# HV_power.net
KiCad netlist of a schematic drawn in Altium Designer
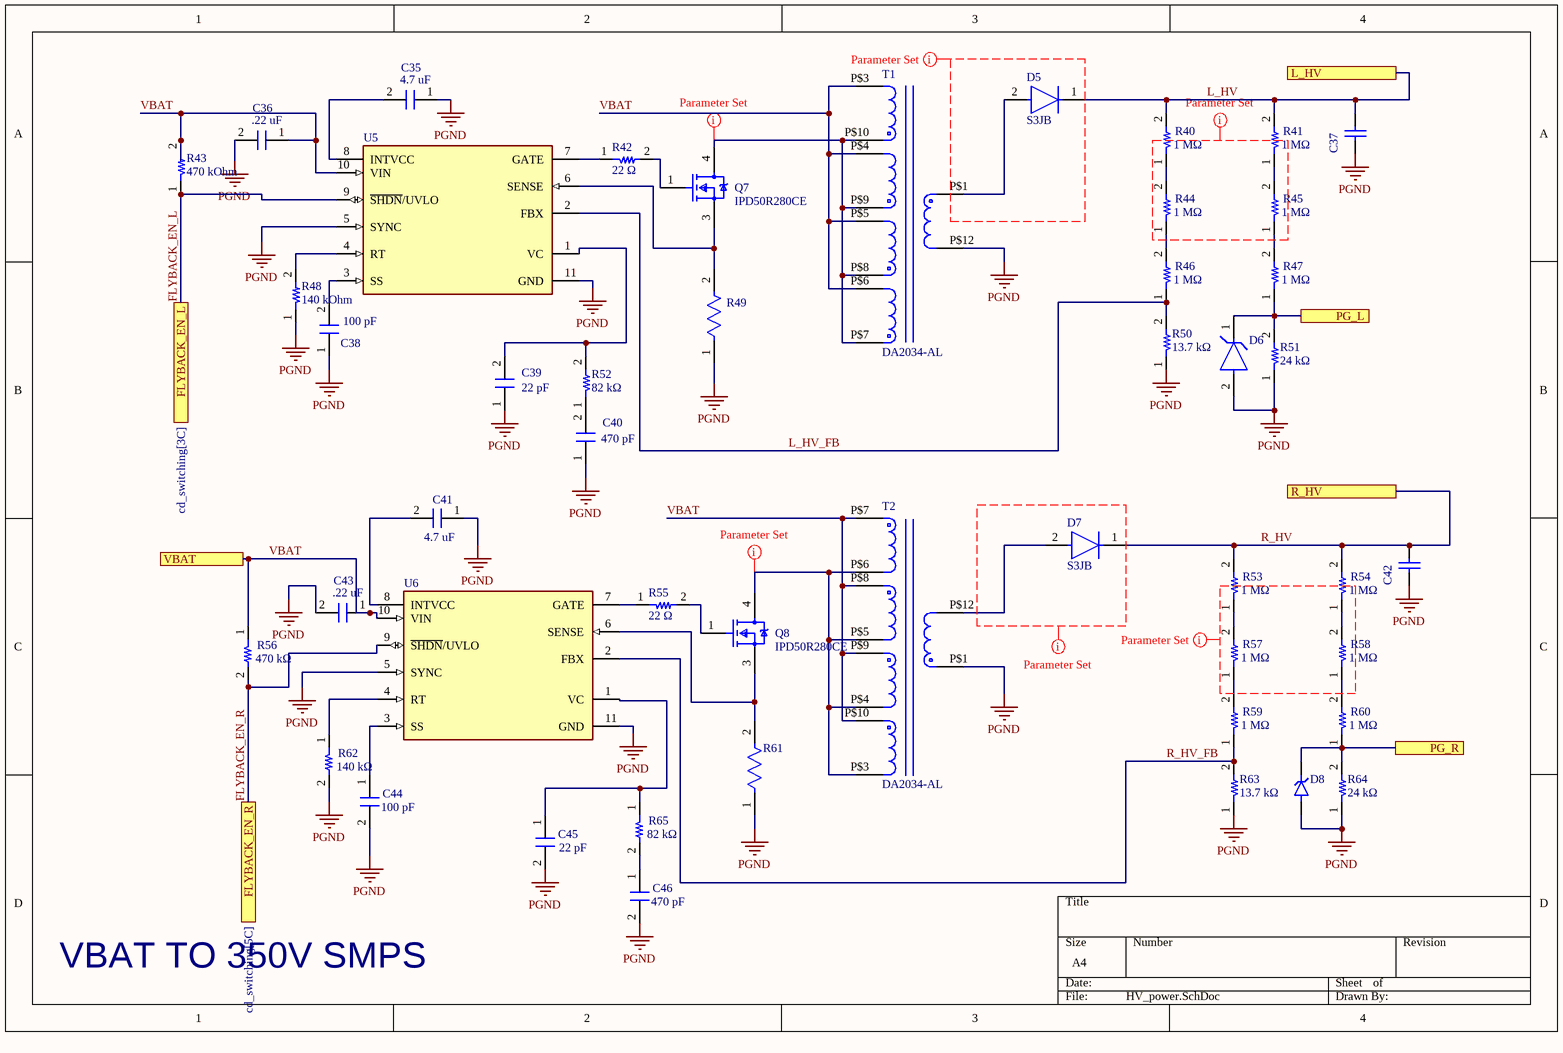
[diagram p0: HV_power.SchDoc]

(export (version "E")
  (design (tool "Eeschema 10.0.6"))
  (components
    (comp (ref "C35")
      (value "4.7 uF")
      (footprint "0603_FP")
      (fields (field (name "Comment") "GRM21BR61C475KA88L"))
      (libsource (lib "RC_sch") (part "Capacitor_0603"))
    )
    (comp (ref "C36")
      (value ".22 uF")
      (footprint "0603_FP")
      (fields (field (name "Comment") "GRM21BR61C475KA88L"))
      (libsource (lib "RC_sch") (part "Capacitor_0603"))
    )
    (comp (ref "C37")
      (value "890283323005CS")
      (footprint "WCAP-FTBP_L13W5.5H11")
      (description "Cap, 0.1Uf, 400V, Film, Radial Rohs Compliant: Yes")
      (libsource (lib "Altium Content Vault") (part "Capacitor_Non-Polarized"))
    )
    (comp (ref "C38")
      (value "100 pF")
      (footprint "0603_FP")
      (fields (field (name "Comment") "Capacitor_0603"))
      (libsource (lib "RC_sch") (part "Capacitor_0603"))
    )
    (comp (ref "C39")
      (value "22 pF")
      (footprint "0603_FP")
      (fields (field (name "Comment") "Capacitor_0603"))
      (libsource (lib "RC_sch") (part "Capacitor_0603"))
    )
    (comp (ref "C40")
      (value "470 pF")
      (footprint "0603_FP")
      (fields (field (name "Comment") "Capacitor_0603"))
      (libsource (lib "RC_sch") (part "Capacitor_0603"))
    )
    (comp (ref "C41")
      (value "4.7 uF")
      (footprint "0603_FP")
      (fields (field (name "Comment") "Capacitor_0603"))
      (libsource (lib "RC_sch") (part "Capacitor_0603"))
    )
    (comp (ref "C42")
      (value "890283323005CS")
      (footprint "WCAP-FTBP_L13W5.5H11")
      (description "Cap, 0.1Uf, 400V, Film, Radial Rohs Compliant: Yes")
      (libsource (lib "Altium Content Vault") (part "Capacitor_Non-Polarized"))
    )
    (comp (ref "C43")
      (value ".22 uF")
      (footprint "0603_FP")
      (fields (field (name "Comment") "GRM21BR61C475KA88L"))
      (libsource (lib "RC_sch") (part "Capacitor_0603"))
    )
    (comp (ref "C44")
      (value "100 pF")
      (footprint "0603_FP")
      (fields (field (name "Comment") "Capacitor_0603"))
      (libsource (lib "RC_sch") (part "Capacitor_0603"))
    )
    (comp (ref "C45")
      (value "22 pF")
      (footprint "0603_FP")
      (fields (field (name "Comment") "Capacitor_0603"))
      (libsource (lib "RC_sch") (part "Capacitor_0603"))
    )
    (comp (ref "C46")
      (value "470 pF")
      (footprint "0603_FP")
      (fields (field (name "Comment") "Capacitor_0603"))
      (libsource (lib "RC_sch") (part "Capacitor_0603"))
    )
    (comp (ref "D5")
      (value "S3JB")
      (footprint "FP-403AF-MFG")
      (description "S3JB Rectifier Diode, 1 Phase, 1 Element, 3A, 600V V(RRM), Silicon, DO-214AA")
      (libsource (lib "Altium Content Vault") (part "e8bb5000357cae87636711d27716c66"))
    )
    (comp (ref "D6")
      (value "CZRQR3V3B-HF")
      (footprint "FP-0402-SOD-923F-MFG")
      (description "DIODE ZENER 3.3V 125MW 0402")
      (fields (field (name "TOLERANCE") "5%"))
      (libsource (lib "Altium Content Vault") (part "f813f71cba58e380607f5dd3caf9714"))
    )
    (comp (ref "D7")
      (value "S3JB")
      (footprint "FP-403AF-MFG")
      (description "S3JB Rectifier Diode, 1 Phase, 1 Element, 3A, 600V V(RRM), Silicon, DO-214AA")
      (libsource (lib "Altium Content Vault") (part "e8bb5000357cae87636711d27716c66"))
    )
    (comp (ref "D8")
      (value "BZT52B15SH_RRG")
      (footprint "DIO_BZT52B15SH_RRG")
      (description "SOD-323, 200mW, 2%, 15V, Zener Diode")
      (fields (field (name "MF") "Taiwan Semiconductor Corporation") (field (name "MP") "BZT52B15SH RRG"))
      (libsource (lib "BZT52B15SH_RRG") (part "BZT52B15SH_RRG"))
    )
    (comp (ref "Q7")
      (value "IPD50R280CE")
      (footprint "FP-PG-TO252-3-MFG")
      (description "MOSFET N-CH 30V 161A DPAK")
      (fields
        (field (name "OCTOPART") "https://octopart.com/irlr7843trpbf-infineon-65875062")
        (field (name "MANUFACTURER PART NUMBER") "IRLR7843TRPBF")
      )
      (libsource (lib "Altium Content Vault") (part "2f21c11e83d30f418bb422e5a3b3d11"))
    )
    (comp (ref "Q8")
      (value "IPD50R280CE")
      (footprint "FP-PG-TO252-3-MFG")
      (description "MOSFET N-CH 30V 161A DPAK")
      (fields
        (field (name "OCTOPART") "https://octopart.com/irlr7843trpbf-infineon-65875062")
        (field (name "MANUFACTURER PART NUMBER") "IRLR7843TRPBF")
      )
      (libsource (lib "Altium Content Vault") (part "2f21c11e83d30f418bb422e5a3b3d11"))
    )
    (comp (ref "R40")
      (value "1 MΩ")
      (footprint "0805_FP")
      (fields (field (name "Comment") "R_0805"))
      (libsource (lib "0805_R") (part "R_0805"))
    )
    (comp (ref "R41")
      (value "1 MΩ")
      (footprint "0805_FP")
      (fields (field (name "Comment") "R_0805"))
      (libsource (lib "0805_R") (part "R_0805"))
    )
    (comp (ref "R42")
      (value "22 Ω")
      (footprint "0603_FP")
      (fields (field (name "Comment") "Resistor_0603"))
      (libsource (lib "RC_sch") (part "Resistor_0603"))
    )
    (comp (ref "R43")
      (value "470 kOhm")
      (footprint "0603_FP")
      (fields (field (name "Comment") "Resistor_0603"))
      (libsource (lib "RC_sch") (part "Resistor_0603"))
    )
    (comp (ref "R44")
      (value "1 MΩ")
      (footprint "0805_FP")
      (fields (field (name "Comment") "R_0805"))
      (libsource (lib "0805_R") (part "R_0805"))
    )
    (comp (ref "R45")
      (value "1 MΩ")
      (footprint "0805_FP")
      (fields (field (name "Comment") "R_0805"))
      (libsource (lib "0805_R") (part "R_0805"))
    )
    (comp (ref "R46")
      (value "1 MΩ")
      (footprint "0805_FP")
      (fields (field (name "Comment") "R_0805"))
      (libsource (lib "0805_R") (part "R_0805"))
    )
    (comp (ref "R47")
      (value "1 MΩ")
      (footprint "0805_FP")
      (fields (field (name "Comment") "R_0805"))
      (libsource (lib "0805_R") (part "R_0805"))
    )
    (comp (ref "R48")
      (value "140 kOhm")
      (footprint "0603_FP")
      (fields (field (name "Comment") "Resistor_0603"))
      (libsource (lib "RC_sch") (part "Resistor_0603"))
    )
    (comp (ref "R49")
      (value "CSRN2010FK20L0")
      (footprint "FP-CSRN2010-IPC_B")
      (description "Res Thick Film 2010 20mΩ 1% 1W ±250ppm/°C Molded SMD Plastic T/R")
      (fields (field (name "TOLERANCE") "1%"))
      (libsource (lib "Altium Content Vault") (part "1029c3af85768c4190bb7ad29bc67b5"))
    )
    (comp (ref "R50")
      (value "13.7 kΩ")
      (footprint "0805_FP")
      (fields (field (name "Comment") "R_0805"))
      (libsource (lib "0805_R") (part "R_0805"))
    )
    (comp (ref "R51")
      (value "24 kΩ")
      (footprint "0805_FP")
      (fields (field (name "Comment") "R_0805"))
      (libsource (lib "0805_R") (part "R_0805"))
    )
    (comp (ref "R52")
      (value "82 kΩ")
      (footprint "0603_FP")
      (fields (field (name "Comment") "Resistor_0603"))
      (libsource (lib "RC_sch") (part "Resistor_0603"))
    )
    (comp (ref "R53")
      (value "1 MΩ")
      (footprint "0805_FP")
      (fields (field (name "Comment") "R_0805"))
      (libsource (lib "0805_R") (part "R_0805"))
    )
    (comp (ref "R54")
      (value "1 MΩ")
      (footprint "0805_FP")
      (fields (field (name "Comment") "R_0805"))
      (libsource (lib "0805_R") (part "R_0805"))
    )
    (comp (ref "R55")
      (value "22 Ω")
      (footprint "0603_FP")
      (fields (field (name "Comment") "Resistor_0603"))
      (libsource (lib "RC_sch") (part "Resistor_0603"))
    )
    (comp (ref "R56")
      (value "470 kΩ")
      (footprint "0603_FP")
      (fields (field (name "Comment") "Resistor_0603"))
      (libsource (lib "RC_sch") (part "Resistor_0603"))
    )
    (comp (ref "R57")
      (value "1 MΩ")
      (footprint "0805_FP")
      (fields (field (name "Comment") "R_0805"))
      (libsource (lib "0805_R") (part "R_0805"))
    )
    (comp (ref "R58")
      (value "1 MΩ")
      (footprint "0805_FP")
      (fields (field (name "Comment") "R_0805"))
      (libsource (lib "0805_R") (part "R_0805"))
    )
    (comp (ref "R59")
      (value "1 MΩ")
      (footprint "0805_FP")
      (fields (field (name "Comment") "R_0805"))
      (libsource (lib "0805_R") (part "R_0805"))
    )
    (comp (ref "R60")
      (value "1 MΩ")
      (footprint "0805_FP")
      (fields (field (name "Comment") "R_0805"))
      (libsource (lib "0805_R") (part "R_0805"))
    )
    (comp (ref "R61")
      (value "CSRN2010FK20L0")
      (footprint "FP-CSRN2010-IPC_B")
      (description "Res Thick Film 2010 20mΩ 1% 1W ±250ppm/°C Molded SMD Plastic T/R")
      (fields (field (name "TOLERANCE") "1%"))
      (libsource (lib "Altium Content Vault") (part "1029c3af85768c4190bb7ad29bc67b5"))
    )
    (comp (ref "R62")
      (value "140 kΩ")
      (footprint "0603_FP")
      (fields (field (name "Comment") "Resistor_0603"))
      (libsource (lib "RC_sch") (part "Resistor_0603"))
    )
    (comp (ref "R63")
      (value "13.7 kΩ")
      (footprint "0805_FP")
      (fields (field (name "Comment") "R_0805"))
      (libsource (lib "0805_R") (part "R_0805"))
    )
    (comp (ref "R64")
      (value "24 kΩ")
      (footprint "0805_FP")
      (fields (field (name "Comment") "R_0805"))
      (libsource (lib "0805_R") (part "R_0805"))
    )
    (comp (ref "R65")
      (value "82 kΩ")
      (footprint "0603_FP")
      (fields (field (name "Comment") "Resistor_0603"))
      (libsource (lib "RC_sch") (part "Resistor_0603"))
    )
    (comp (ref "T1")
      (value "DA2034-AL")
      (footprint "DA2034-AL")
      (libsource (lib "DA2034-AL") (part "DA2034-AL"))
    )
    (comp (ref "T2")
      (value "DA2034-AL")
      (footprint "DA2034-AL")
      (libsource (lib "DA2034-AL") (part "DA2034-AL"))
    )
    (comp (ref "U5")
      (value "LT3758EDD#PBF")
      (footprint "FP-DD-10-05-08-1699-IPC_B")
      (description "IC REG CTRLR MULT TOPOLOGY 10DFN")
      (libsource (lib "Altium Content Vault") (part "079e3863d39c5e5796f69dc810f510e"))
    )
    (comp (ref "U6")
      (value "LT3758EDD#PBF")
      (footprint "FP-DD-10-05-08-1699-IPC_B")
      (description "IC REG CTRLR MULT TOPOLOGY 10DFN")
      (libsource (lib "Altium Content Vault") (part "079e3863d39c5e5796f69dc810f510e"))
    )
  )
  (nets
    (net (code "1") (name "/FLYBACK_EN_L") (class "Default")
      (node (ref "R43") (pin "1") (pinfunction "1_1") (pintype "passive"))
      (node (ref "U5") (pin "9") (pinfunction "~{SHDN}/UVLO_9") (pintype "bidirectional"))
    )
    (net (code "2") (name "/FLYBACK_EN_R") (class "Default")
      (node (ref "R56") (pin "2") (pinfunction "2_2") (pintype "passive"))
      (node (ref "U6") (pin "9") (pinfunction "~{SHDN}/UVLO_9") (pintype "bidirectional"))
    )
    (net (code "3") (name "/L_HV") (class "Default")
      (node (ref "C37") (pin "2") (pinfunction "2_2") (pintype "passive"))
      (node (ref "D5") (pin "1") (pinfunction "C_1") (pintype "passive"))
      (node (ref "R40") (pin "2") (pinfunction "2_2") (pintype "passive"))
      (node (ref "R41") (pin "2") (pinfunction "2_2") (pintype "passive"))
    )
    (net (code "4") (name "/L_HV_FB") (class "Default")
      (node (ref "R46") (pin "1") (pinfunction "1_1") (pintype "passive"))
      (node (ref "R50") (pin "2") (pinfunction "2_2") (pintype "passive"))
      (node (ref "U5") (pin "2") (pinfunction "FBX_2") (pintype "passive"))
    )
    (net (code "5") (name "/PG_L") (class "Default")
      (node (ref "D6") (pin "1") (pinfunction "C_1") (pintype "passive"))
      (node (ref "R47") (pin "1") (pinfunction "1_1") (pintype "passive"))
      (node (ref "R51") (pin "2") (pinfunction "2_2") (pintype "passive"))
    )
    (net (code "6") (name "/PG_R") (class "Default")
      (node (ref "D8") (pin "1") (pinfunction "K_1") (pintype "passive"))
      (node (ref "R60") (pin "1") (pinfunction "1_1") (pintype "passive"))
      (node (ref "R64") (pin "2") (pinfunction "2_2") (pintype "passive"))
    )
    (net (code "7") (name "/R_HV") (class "Default")
      (node (ref "C42") (pin "2") (pinfunction "2_2") (pintype "passive"))
      (node (ref "D7") (pin "1") (pinfunction "C_1") (pintype "passive"))
      (node (ref "R53") (pin "2") (pinfunction "2_2") (pintype "passive"))
      (node (ref "R54") (pin "2") (pinfunction "2_2") (pintype "passive"))
    )
    (net (code "8") (name "/R_HV_FB") (class "Default")
      (node (ref "R59") (pin "1") (pinfunction "1_1") (pintype "passive"))
      (node (ref "R63") (pin "2") (pinfunction "2_2") (pintype "passive"))
      (node (ref "U6") (pin "2") (pinfunction "FBX_2") (pintype "passive"))
    )
    (net (code "9") (name "/VBAT") (class "Default")
      (node (ref "C36") (pin "1") (pinfunction "1_1") (pintype "passive"))
      (node (ref "C43") (pin "1") (pinfunction "1_1") (pintype "passive"))
      (node (ref "R43") (pin "2") (pinfunction "2_2") (pintype "passive"))
      (node (ref "R56") (pin "1") (pinfunction "1_1") (pintype "passive"))
      (node (ref "T1") (pin "P$3") (pinfunction "3_P$3") (pintype "passive"))
      (node (ref "T1") (pin "P$4") (pinfunction "4_P$4") (pintype "passive"))
      (node (ref "T1") (pin "P$5") (pinfunction "5_P$5") (pintype "passive"))
      (node (ref "T1") (pin "P$6") (pinfunction "6_P$6") (pintype "passive"))
      (node (ref "T2") (pin "P$10") (pinfunction "10_P$10") (pintype "passive"))
      (node (ref "T2") (pin "P$7") (pinfunction "7_P$7") (pintype "passive"))
      (node (ref "T2") (pin "P$8") (pinfunction "8_P$8") (pintype "passive"))
      (node (ref "T2") (pin "P$9") (pinfunction "9_P$9") (pintype "passive"))
      (node (ref "U5") (pin "10") (pinfunction "VIN_10") (pintype "input"))
      (node (ref "U6") (pin "10") (pinfunction "VIN_10") (pintype "input"))
    )
    (net (code "10") (name "Net-(C40-Pad2)") (class "Default")
      (node (ref "C40") (pin "2") (pinfunction "2_2") (pintype "passive"))
      (node (ref "R52") (pin "1") (pinfunction "1_1") (pintype "passive"))
    )
    (net (code "11") (name "Net-(C46-Pad1)") (class "Default")
      (node (ref "C46") (pin "1") (pinfunction "1_1") (pintype "passive"))
      (node (ref "R65") (pin "2") (pinfunction "2_2") (pintype "passive"))
    )
    (net (code "12") (name "Net-(D5-A)") (class "Default")
      (node (ref "D5") (pin "2") (pinfunction "A_2") (pintype "passive"))
      (node (ref "T1") (pin "P$1") (pinfunction "1_P$1") (pintype "passive"))
    )
    (net (code "13") (name "Net-(D7-A)") (class "Default")
      (node (ref "D7") (pin "2") (pinfunction "A_2") (pintype "passive"))
      (node (ref "T2") (pin "P$12") (pinfunction "12_P$12") (pintype "passive"))
    )
    (net (code "14") (name "Net-(Q7-DRAIN)") (class "Default")
      (node (ref "Q7") (pin "4") (pinfunction "DRAIN_4") (pintype "passive"))
      (node (ref "T1") (pin "P$10") (pinfunction "10_P$10") (pintype "passive"))
      (node (ref "T1") (pin "P$7") (pinfunction "7_P$7") (pintype "passive"))
      (node (ref "T1") (pin "P$8") (pinfunction "8_P$8") (pintype "passive"))
      (node (ref "T1") (pin "P$9") (pinfunction "9_P$9") (pintype "passive"))
    )
    (net (code "15") (name "Net-(Q7-GATE)") (class "Default")
      (node (ref "Q7") (pin "1") (pinfunction "GATE_1") (pintype "passive"))
      (node (ref "R42") (pin "2") (pinfunction "2_2") (pintype "passive"))
    )
    (net (code "16") (name "Net-(Q7-SOURCE)") (class "Default")
      (node (ref "Q7") (pin "3") (pinfunction "SOURCE_3") (pintype "passive"))
      (node (ref "R49") (pin "2") (pinfunction "2_2") (pintype "passive"))
      (node (ref "U5") (pin "6") (pinfunction "SENSE_6") (pintype "input"))
    )
    (net (code "17") (name "Net-(Q8-DRAIN)") (class "Default")
      (node (ref "Q8") (pin "4") (pinfunction "DRAIN_4") (pintype "passive"))
      (node (ref "T2") (pin "P$3") (pinfunction "3_P$3") (pintype "passive"))
      (node (ref "T2") (pin "P$4") (pinfunction "4_P$4") (pintype "passive"))
      (node (ref "T2") (pin "P$5") (pinfunction "5_P$5") (pintype "passive"))
      (node (ref "T2") (pin "P$6") (pinfunction "6_P$6") (pintype "passive"))
    )
    (net (code "18") (name "Net-(Q8-GATE)") (class "Default")
      (node (ref "Q8") (pin "1") (pinfunction "GATE_1") (pintype "passive"))
      (node (ref "R55") (pin "2") (pinfunction "2_2") (pintype "passive"))
    )
    (net (code "19") (name "Net-(Q8-SOURCE)") (class "Default")
      (node (ref "Q8") (pin "3") (pinfunction "SOURCE_3") (pintype "passive"))
      (node (ref "R61") (pin "2") (pinfunction "2_2") (pintype "passive"))
      (node (ref "U6") (pin "6") (pinfunction "SENSE_6") (pintype "input"))
    )
    (net (code "20") (name "Net-(R40-Pad1)") (class "Default")
      (node (ref "R40") (pin "1") (pinfunction "1_1") (pintype "passive"))
      (node (ref "R44") (pin "2") (pinfunction "2_2") (pintype "passive"))
    )
    (net (code "21") (name "Net-(R41-Pad1)") (class "Default")
      (node (ref "R41") (pin "1") (pinfunction "1_1") (pintype "passive"))
      (node (ref "R45") (pin "2") (pinfunction "2_2") (pintype "passive"))
    )
    (net (code "22") (name "Net-(R44-Pad1)") (class "Default")
      (node (ref "R44") (pin "1") (pinfunction "1_1") (pintype "passive"))
      (node (ref "R46") (pin "2") (pinfunction "2_2") (pintype "passive"))
    )
    (net (code "23") (name "Net-(R45-Pad1)") (class "Default")
      (node (ref "R45") (pin "1") (pinfunction "1_1") (pintype "passive"))
      (node (ref "R47") (pin "2") (pinfunction "2_2") (pintype "passive"))
    )
    (net (code "24") (name "Net-(R53-Pad1)") (class "Default")
      (node (ref "R53") (pin "1") (pinfunction "1_1") (pintype "passive"))
      (node (ref "R57") (pin "2") (pinfunction "2_2") (pintype "passive"))
    )
    (net (code "25") (name "Net-(R54-Pad1)") (class "Default")
      (node (ref "R54") (pin "1") (pinfunction "1_1") (pintype "passive"))
      (node (ref "R58") (pin "2") (pinfunction "2_2") (pintype "passive"))
    )
    (net (code "26") (name "Net-(R57-Pad1)") (class "Default")
      (node (ref "R57") (pin "1") (pinfunction "1_1") (pintype "passive"))
      (node (ref "R59") (pin "2") (pinfunction "2_2") (pintype "passive"))
    )
    (net (code "27") (name "Net-(R58-Pad1)") (class "Default")
      (node (ref "R58") (pin "1") (pinfunction "1_1") (pintype "passive"))
      (node (ref "R60") (pin "2") (pinfunction "2_2") (pintype "passive"))
    )
    (net (code "28") (name "Net-(U5-GATE)") (class "Default")
      (node (ref "R42") (pin "1") (pinfunction "1_1") (pintype "passive"))
      (node (ref "U5") (pin "7") (pinfunction "GATE_7") (pintype "passive"))
    )
    (net (code "29") (name "Net-(U5-INTVCC)") (class "Default")
      (node (ref "C35") (pin "2") (pinfunction "2_2") (pintype "passive"))
      (node (ref "U5") (pin "8") (pinfunction "INTVCC_8") (pintype "power_in"))
    )
    (net (code "30") (name "Net-(U5-RT)") (class "Default")
      (node (ref "R48") (pin "2") (pinfunction "2_2") (pintype "passive"))
      (node (ref "U5") (pin "4") (pinfunction "RT_4") (pintype "input"))
    )
    (net (code "31") (name "Net-(U5-SS)") (class "Default")
      (node (ref "C38") (pin "2") (pinfunction "2_2") (pintype "passive"))
      (node (ref "U5") (pin "3") (pinfunction "SS_3") (pintype "input"))
    )
    (net (code "32") (name "Net-(U5-VC)") (class "Default")
      (node (ref "C39") (pin "2") (pinfunction "2_2") (pintype "passive"))
      (node (ref "R52") (pin "2") (pinfunction "2_2") (pintype "passive"))
      (node (ref "U5") (pin "1") (pinfunction "VC_1") (pintype "passive"))
    )
    (net (code "33") (name "Net-(U6-GATE)") (class "Default")
      (node (ref "R55") (pin "1") (pinfunction "1_1") (pintype "passive"))
      (node (ref "U6") (pin "7") (pinfunction "GATE_7") (pintype "passive"))
    )
    (net (code "34") (name "Net-(U6-INTVCC)") (class "Default")
      (node (ref "C41") (pin "2") (pinfunction "2_2") (pintype "passive"))
      (node (ref "U6") (pin "8") (pinfunction "INTVCC_8") (pintype "power_in"))
    )
    (net (code "35") (name "Net-(U6-RT)") (class "Default")
      (node (ref "R62") (pin "1") (pinfunction "1_1") (pintype "passive"))
      (node (ref "U6") (pin "4") (pinfunction "RT_4") (pintype "input"))
    )
    (net (code "36") (name "Net-(U6-SS)") (class "Default")
      (node (ref "C44") (pin "1") (pinfunction "1_1") (pintype "passive"))
      (node (ref "U6") (pin "3") (pinfunction "SS_3") (pintype "input"))
    )
    (net (code "37") (name "Net-(U6-VC)") (class "Default")
      (node (ref "C45") (pin "1") (pinfunction "1_1") (pintype "passive"))
      (node (ref "R65") (pin "1") (pinfunction "1_1") (pintype "passive"))
      (node (ref "U6") (pin "1") (pinfunction "VC_1") (pintype "passive"))
    )
    (net (code "38") (name "PGND") (class "Default")
      (node (ref "C35") (pin "1") (pinfunction "1_1") (pintype "passive"))
      (node (ref "C36") (pin "2") (pinfunction "2_2") (pintype "passive"))
      (node (ref "C37") (pin "1") (pinfunction "1_1") (pintype "passive"))
      (node (ref "C38") (pin "1") (pinfunction "1_1") (pintype "passive"))
      (node (ref "C39") (pin "1") (pinfunction "1_1") (pintype "passive"))
      (node (ref "C40") (pin "1") (pinfunction "1_1") (pintype "passive"))
      (node (ref "C41") (pin "1") (pinfunction "1_1") (pintype "passive"))
      (node (ref "C42") (pin "1") (pinfunction "1_1") (pintype "passive"))
      (node (ref "C43") (pin "2") (pinfunction "2_2") (pintype "passive"))
      (node (ref "C44") (pin "2") (pinfunction "2_2") (pintype "passive"))
      (node (ref "C45") (pin "2") (pinfunction "2_2") (pintype "passive"))
      (node (ref "C46") (pin "2") (pinfunction "2_2") (pintype "passive"))
      (node (ref "D6") (pin "2") (pinfunction "A_2") (pintype "passive"))
      (node (ref "D8") (pin "2") (pinfunction "A_2") (pintype "passive"))
      (node (ref "R48") (pin "1") (pinfunction "1_1") (pintype "passive"))
      (node (ref "R49") (pin "1") (pinfunction "1_1") (pintype "passive"))
      (node (ref "R50") (pin "1") (pinfunction "1_1") (pintype "passive"))
      (node (ref "R51") (pin "1") (pinfunction "1_1") (pintype "passive"))
      (node (ref "R61") (pin "1") (pinfunction "1_1") (pintype "passive"))
      (node (ref "R62") (pin "2") (pinfunction "2_2") (pintype "passive"))
      (node (ref "R63") (pin "1") (pinfunction "1_1") (pintype "passive"))
      (node (ref "R64") (pin "1") (pinfunction "1_1") (pintype "passive"))
      (node (ref "T1") (pin "P$12") (pinfunction "12_P$12") (pintype "passive"))
      (node (ref "T2") (pin "P$1") (pinfunction "1_P$1") (pintype "passive"))
      (node (ref "U5") (pin "11") (pinfunction "GND_11") (pintype "power_in"))
      (node (ref "U5") (pin "5") (pinfunction "SYNC_5") (pintype "input"))
      (node (ref "U6") (pin "11") (pinfunction "GND_11") (pintype "power_in"))
      (node (ref "U6") (pin "5") (pinfunction "SYNC_5") (pintype "input"))
    )
  )
)
